# Bypass_FPGA_3V3.net
KiCad netlist of a schematic drawn in Altium Designer
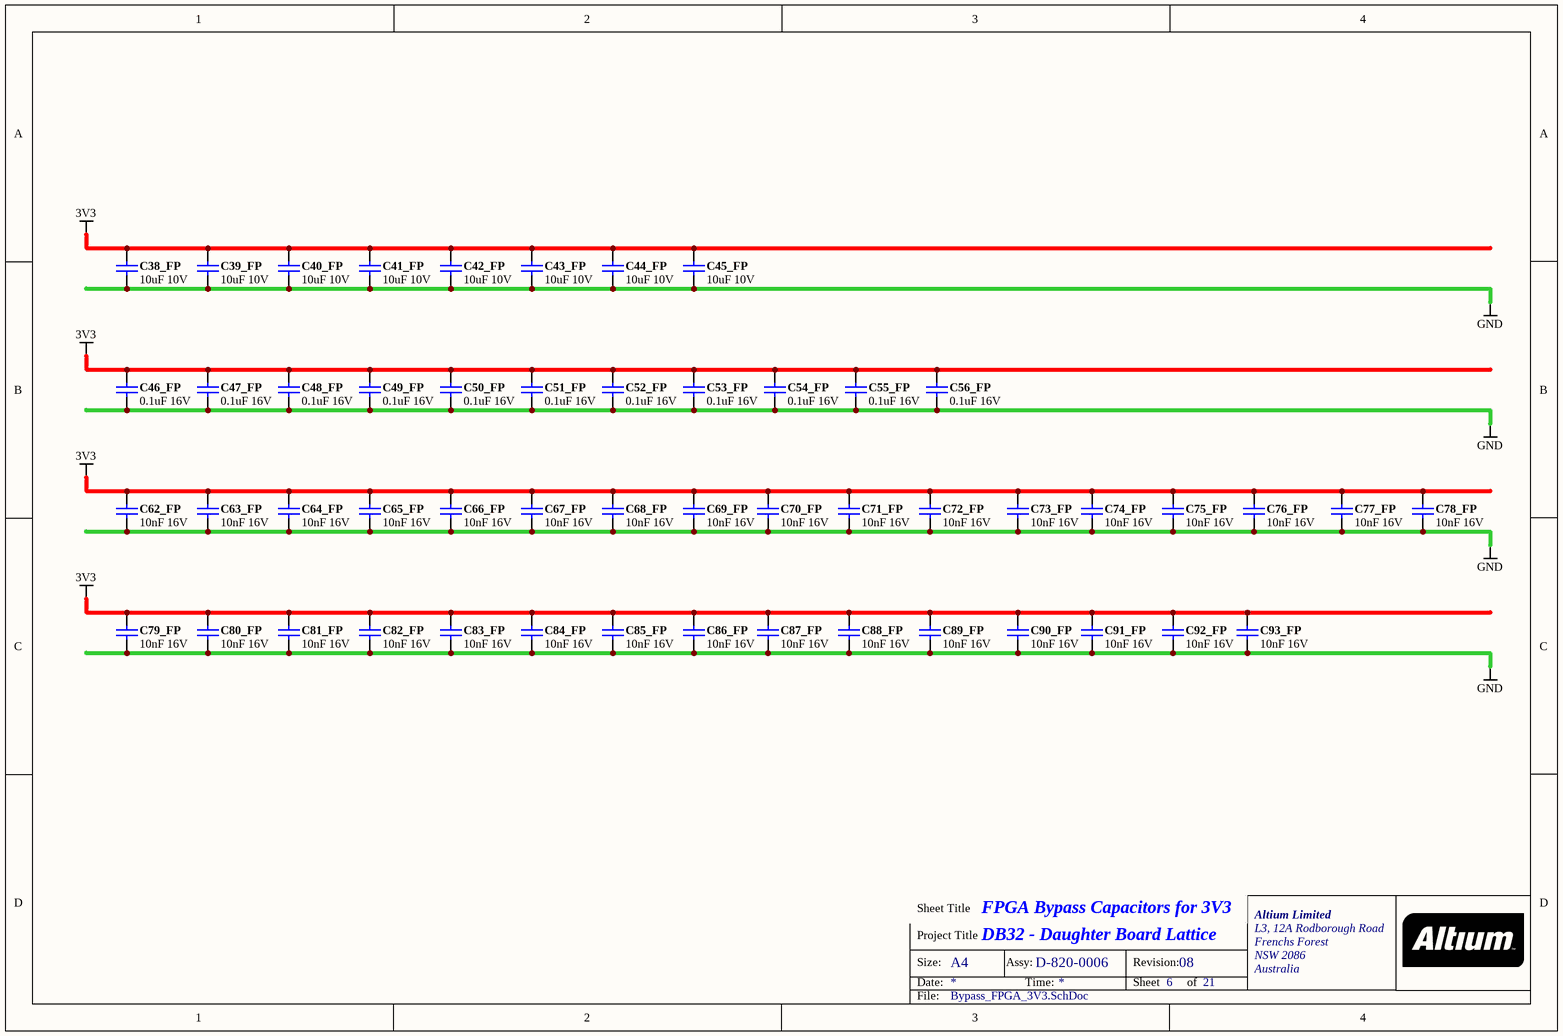
[diagram p0: Bypass_FPGA_3V3.SchDoc]

(export (version "E")
  (design (tool "Eeschema 10.0.6"))
  (components
    (comp (ref "C38_FP")
      (value "10uF 10V")
      (footprint "CAPC2012-STAR")
      (description "Capacitor, Ceramic, 10uF 10% 10V 0805 (2012) X5R")
      (fields (field (name "TOLERANCE") "10 %"))
      (libsource (lib "AltiumDesignLibrary") (part "CAP-NP"))
    )
    (comp (ref "C39_FP")
      (value "10uF 10V")
      (footprint "CAPC2012-STAR")
      (description "Capacitor, Ceramic, 10uF 10% 10V 0805 (2012) X5R")
      (fields (field (name "TOLERANCE") "10 %"))
      (libsource (lib "AltiumDesignLibrary") (part "CAP-NP"))
    )
    (comp (ref "C40_FP")
      (value "10uF 10V")
      (footprint "CAPC2012-STAR")
      (description "Capacitor, Ceramic, 10uF 10% 10V 0805 (2012) X5R")
      (fields (field (name "TOLERANCE") "10 %"))
      (libsource (lib "AltiumDesignLibrary") (part "CAP-NP"))
    )
    (comp (ref "C41_FP")
      (value "10uF 10V")
      (footprint "CAPC2012-STAR")
      (description "Capacitor, Ceramic, 10uF 10% 10V 0805 (2012) X5R")
      (fields (field (name "TOLERANCE") "10 %"))
      (libsource (lib "AltiumDesignLibrary") (part "CAP-NP"))
    )
    (comp (ref "C42_FP")
      (value "10uF 10V")
      (footprint "CAPC2012-STAR")
      (description "Capacitor, Ceramic, 10uF 10% 10V 0805 (2012) X5R")
      (fields (field (name "TOLERANCE") "10 %"))
      (libsource (lib "AltiumDesignLibrary") (part "CAP-NP"))
    )
    (comp (ref "C43_FP")
      (value "10uF 10V")
      (footprint "CAPC2012-STAR")
      (description "Capacitor, Ceramic, 10uF 10% 10V 0805 (2012) X5R")
      (fields (field (name "TOLERANCE") "10 %"))
      (libsource (lib "AltiumDesignLibrary") (part "CAP-NP"))
    )
    (comp (ref "C44_FP")
      (value "10uF 10V")
      (footprint "CAPC2012-STAR")
      (description "Capacitor, Ceramic, 10uF 10% 10V 0805 (2012) X5R")
      (fields (field (name "TOLERANCE") "10 %"))
      (libsource (lib "AltiumDesignLibrary") (part "CAP-NP"))
    )
    (comp (ref "C45_FP")
      (value "10uF 10V")
      (footprint "CAPC2012-STAR")
      (description "Capacitor, Ceramic, 10uF 10% 10V 0805 (2012) X5R")
      (fields (field (name "TOLERANCE") "10 %"))
      (libsource (lib "AltiumDesignLibrary") (part "CAP-NP"))
    )
    (comp (ref "C46_FP")
      (value "0.1uF 16V")
      (footprint "CAPC1005-STAR")
      (description "Capacitor, Ceramic, 0.1uF 10% 16V 0402 (1005) X7R")
      (fields (field (name "TOLERANCE") "10 %"))
      (libsource (lib "AltiumDesignLibrary") (part "CAP-NP"))
    )
    (comp (ref "C47_FP")
      (value "0.1uF 16V")
      (footprint "CAPC1005-STAR")
      (description "Capacitor, Ceramic, 0.1uF 10% 16V 0402 (1005) X7R")
      (fields (field (name "TOLERANCE") "10 %"))
      (libsource (lib "AltiumDesignLibrary") (part "CAP-NP"))
    )
    (comp (ref "C48_FP")
      (value "0.1uF 16V")
      (footprint "CAPC1005-STAR")
      (description "Capacitor, Ceramic, 0.1uF 10% 16V 0402 (1005) X7R")
      (fields (field (name "TOLERANCE") "10 %"))
      (libsource (lib "AltiumDesignLibrary") (part "CAP-NP"))
    )
    (comp (ref "C49_FP")
      (value "0.1uF 16V")
      (footprint "CAPC1005-STAR")
      (description "Capacitor, Ceramic, 0.1uF 10% 16V 0402 (1005) X7R")
      (fields (field (name "TOLERANCE") "10 %"))
      (libsource (lib "AltiumDesignLibrary") (part "CAP-NP"))
    )
    (comp (ref "C50_FP")
      (value "0.1uF 16V")
      (footprint "CAPC1005-STAR")
      (description "Capacitor, Ceramic, 0.1uF 10% 16V 0402 (1005) X7R")
      (fields (field (name "TOLERANCE") "10 %"))
      (libsource (lib "AltiumDesignLibrary") (part "CAP-NP"))
    )
    (comp (ref "C51_FP")
      (value "0.1uF 16V")
      (footprint "CAPC1005-STAR")
      (description "Capacitor, Ceramic, 0.1uF 10% 16V 0402 (1005) X7R")
      (fields (field (name "TOLERANCE") "10 %"))
      (libsource (lib "AltiumDesignLibrary") (part "CAP-NP"))
    )
    (comp (ref "C52_FP")
      (value "0.1uF 16V")
      (footprint "CAPC1005-STAR")
      (description "Capacitor, Ceramic, 0.1uF 10% 16V 0402 (1005) X7R")
      (fields (field (name "TOLERANCE") "10 %"))
      (libsource (lib "AltiumDesignLibrary") (part "CAP-NP"))
    )
    (comp (ref "C53_FP")
      (value "0.1uF 16V")
      (footprint "CAPC1005-STAR")
      (description "Capacitor, Ceramic, 0.1uF 10% 16V 0402 (1005) X7R")
      (fields (field (name "TOLERANCE") "10 %"))
      (libsource (lib "AltiumDesignLibrary") (part "CAP-NP"))
    )
    (comp (ref "C54_FP")
      (value "0.1uF 16V")
      (footprint "CAPC1005-STAR")
      (description "Capacitor, Ceramic, 0.1uF 10% 16V 0402 (1005) X7R")
      (fields (field (name "TOLERANCE") "10 %"))
      (libsource (lib "AltiumDesignLibrary") (part "CAP-NP"))
    )
    (comp (ref "C55_FP")
      (value "0.1uF 16V")
      (footprint "CAPC1005-STAR")
      (description "Capacitor, Ceramic, 0.1uF 10% 16V 0402 (1005) X7R")
      (fields (field (name "TOLERANCE") "10 %"))
      (libsource (lib "AltiumDesignLibrary") (part "CAP-NP"))
    )
    (comp (ref "C56_FP")
      (value "0.1uF 16V")
      (footprint "CAPC1005-STAR")
      (description "Capacitor, Ceramic, 0.1uF 10% 16V 0402 (1005) X7R")
      (fields (field (name "TOLERANCE") "10 %"))
      (libsource (lib "AltiumDesignLibrary") (part "CAP-NP"))
    )
    (comp (ref "C62_FP")
      (value "10nF 16V")
      (footprint "CAPC1005-STAR")
      (description "Capacitor, Ceramic, 10nF 10% 16V 0402 (1005) X7R")
      (fields (field (name "TOLERANCE") "10 %"))
      (libsource (lib "AltiumDesignLibrary") (part "CAP-NP"))
    )
    (comp (ref "C63_FP")
      (value "10nF 16V")
      (footprint "CAPC1005-STAR")
      (description "Capacitor, Ceramic, 10nF 10% 16V 0402 (1005) X7R")
      (fields (field (name "TOLERANCE") "10 %"))
      (libsource (lib "AltiumDesignLibrary") (part "CAP-NP"))
    )
    (comp (ref "C64_FP")
      (value "10nF 16V")
      (footprint "CAPC1005-STAR")
      (description "Capacitor, Ceramic, 10nF 10% 16V 0402 (1005) X7R")
      (fields (field (name "TOLERANCE") "10 %"))
      (libsource (lib "AltiumDesignLibrary") (part "CAP-NP"))
    )
    (comp (ref "C65_FP")
      (value "10nF 16V")
      (footprint "CAPC1005-STAR")
      (description "Capacitor, Ceramic, 10nF 10% 16V 0402 (1005) X7R")
      (fields (field (name "TOLERANCE") "10 %"))
      (libsource (lib "AltiumDesignLibrary") (part "CAP-NP"))
    )
    (comp (ref "C66_FP")
      (value "10nF 16V")
      (footprint "CAPC1005-STAR")
      (description "Capacitor, Ceramic, 10nF 10% 16V 0402 (1005) X7R")
      (fields (field (name "TOLERANCE") "10 %"))
      (libsource (lib "AltiumDesignLibrary") (part "CAP-NP"))
    )
    (comp (ref "C67_FP")
      (value "10nF 16V")
      (footprint "CAPC1005-STAR")
      (description "Capacitor, Ceramic, 10nF 10% 16V 0402 (1005) X7R")
      (fields (field (name "TOLERANCE") "10 %"))
      (libsource (lib "AltiumDesignLibrary") (part "CAP-NP"))
    )
    (comp (ref "C68_FP")
      (value "10nF 16V")
      (footprint "CAPC1005-STAR")
      (description "Capacitor, Ceramic, 10nF 10% 16V 0402 (1005) X7R")
      (fields (field (name "TOLERANCE") "10 %"))
      (libsource (lib "AltiumDesignLibrary") (part "CAP-NP"))
    )
    (comp (ref "C69_FP")
      (value "10nF 16V")
      (footprint "CAPC1005-STAR")
      (description "Capacitor, Ceramic, 10nF 10% 16V 0402 (1005) X7R")
      (fields (field (name "TOLERANCE") "10 %"))
      (libsource (lib "AltiumDesignLibrary") (part "CAP-NP"))
    )
    (comp (ref "C70_FP")
      (value "10nF 16V")
      (footprint "CAPC1005-STAR")
      (description "Capacitor, Ceramic, 10nF 10% 16V 0402 (1005) X7R")
      (fields (field (name "TOLERANCE") "10 %"))
      (libsource (lib "AltiumDesignLibrary") (part "CAP-NP"))
    )
    (comp (ref "C71_FP")
      (value "10nF 16V")
      (footprint "CAPC1005-STAR")
      (description "Capacitor, Ceramic, 10nF 10% 16V 0402 (1005) X7R")
      (fields (field (name "TOLERANCE") "10 %"))
      (libsource (lib "AltiumDesignLibrary") (part "CAP-NP"))
    )
    (comp (ref "C72_FP")
      (value "10nF 16V")
      (footprint "CAPC1005-STAR")
      (description "Capacitor, Ceramic, 10nF 10% 16V 0402 (1005) X7R")
      (fields (field (name "TOLERANCE") "10 %"))
      (libsource (lib "AltiumDesignLibrary") (part "CAP-NP"))
    )
    (comp (ref "C73_FP")
      (value "10nF 16V")
      (footprint "CAPC1005-STAR")
      (description "Capacitor, Ceramic, 10nF 10% 16V 0402 (1005) X7R")
      (fields (field (name "TOLERANCE") "10 %"))
      (libsource (lib "AltiumDesignLibrary") (part "CAP-NP"))
    )
    (comp (ref "C74_FP")
      (value "10nF 16V")
      (footprint "CAPC1005-STAR")
      (description "Capacitor, Ceramic, 10nF 10% 16V 0402 (1005) X7R")
      (fields (field (name "TOLERANCE") "10 %"))
      (libsource (lib "AltiumDesignLibrary") (part "CAP-NP"))
    )
    (comp (ref "C75_FP")
      (value "10nF 16V")
      (footprint "CAPC1005-STAR")
      (description "Capacitor, Ceramic, 10nF 10% 16V 0402 (1005) X7R")
      (fields (field (name "TOLERANCE") "10 %"))
      (libsource (lib "AltiumDesignLibrary") (part "CAP-NP"))
    )
    (comp (ref "C76_FP")
      (value "10nF 16V")
      (footprint "CAPC1005-STAR")
      (description "Capacitor, Ceramic, 10nF 10% 16V 0402 (1005) X7R")
      (fields (field (name "TOLERANCE") "10 %"))
      (libsource (lib "AltiumDesignLibrary") (part "CAP-NP"))
    )
    (comp (ref "C77_FP")
      (value "10nF 16V")
      (footprint "CAPC1005-STAR")
      (description "Capacitor, Ceramic, 10nF 10% 16V 0402 (1005) X7R")
      (fields (field (name "TOLERANCE") "10 %"))
      (libsource (lib "AltiumDesignLibrary") (part "CAP-NP"))
    )
    (comp (ref "C78_FP")
      (value "10nF 16V")
      (footprint "CAPC1005-STAR")
      (description "Capacitor, Ceramic, 10nF 10% 16V 0402 (1005) X7R")
      (fields (field (name "TOLERANCE") "10 %"))
      (libsource (lib "AltiumDesignLibrary") (part "CAP-NP"))
    )
    (comp (ref "C79_FP")
      (value "10nF 16V")
      (footprint "CAPC1005-STAR")
      (description "Capacitor, Ceramic, 10nF 10% 16V 0402 (1005) X7R")
      (fields (field (name "TOLERANCE") "10 %"))
      (libsource (lib "AltiumDesignLibrary") (part "CAP-NP"))
    )
    (comp (ref "C80_FP")
      (value "10nF 16V")
      (footprint "CAPC1005-STAR")
      (description "Capacitor, Ceramic, 10nF 10% 16V 0402 (1005) X7R")
      (fields (field (name "TOLERANCE") "10 %"))
      (libsource (lib "AltiumDesignLibrary") (part "CAP-NP"))
    )
    (comp (ref "C81_FP")
      (value "10nF 16V")
      (footprint "CAPC1005-STAR")
      (description "Capacitor, Ceramic, 10nF 10% 16V 0402 (1005) X7R")
      (fields (field (name "TOLERANCE") "10 %"))
      (libsource (lib "AltiumDesignLibrary") (part "CAP-NP"))
    )
    (comp (ref "C82_FP")
      (value "10nF 16V")
      (footprint "CAPC1005-STAR")
      (description "Capacitor, Ceramic, 10nF 10% 16V 0402 (1005) X7R")
      (fields (field (name "TOLERANCE") "10 %"))
      (libsource (lib "AltiumDesignLibrary") (part "CAP-NP"))
    )
    (comp (ref "C83_FP")
      (value "10nF 16V")
      (footprint "CAPC1005-STAR")
      (description "Capacitor, Ceramic, 10nF 10% 16V 0402 (1005) X7R")
      (fields (field (name "TOLERANCE") "10 %"))
      (libsource (lib "AltiumDesignLibrary") (part "CAP-NP"))
    )
    (comp (ref "C84_FP")
      (value "10nF 16V")
      (footprint "CAPC1005-STAR")
      (description "Capacitor, Ceramic, 10nF 10% 16V 0402 (1005) X7R")
      (fields (field (name "TOLERANCE") "10 %"))
      (libsource (lib "AltiumDesignLibrary") (part "CAP-NP"))
    )
    (comp (ref "C85_FP")
      (value "10nF 16V")
      (footprint "CAPC1005-STAR")
      (description "Capacitor, Ceramic, 10nF 10% 16V 0402 (1005) X7R")
      (fields (field (name "TOLERANCE") "10 %"))
      (libsource (lib "AltiumDesignLibrary") (part "CAP-NP"))
    )
    (comp (ref "C86_FP")
      (value "10nF 16V")
      (footprint "CAPC1005-STAR")
      (description "Capacitor, Ceramic, 10nF 10% 16V 0402 (1005) X7R")
      (fields (field (name "TOLERANCE") "10 %"))
      (libsource (lib "AltiumDesignLibrary") (part "CAP-NP"))
    )
    (comp (ref "C87_FP")
      (value "10nF 16V")
      (footprint "CAPC1005-STAR")
      (description "Capacitor, Ceramic, 10nF 10% 16V 0402 (1005) X7R")
      (fields (field (name "TOLERANCE") "10 %"))
      (libsource (lib "AltiumDesignLibrary") (part "CAP-NP"))
    )
    (comp (ref "C88_FP")
      (value "10nF 16V")
      (footprint "CAPC1005-STAR")
      (description "Capacitor, Ceramic, 10nF 10% 16V 0402 (1005) X7R")
      (fields (field (name "TOLERANCE") "10 %"))
      (libsource (lib "AltiumDesignLibrary") (part "CAP-NP"))
    )
    (comp (ref "C89_FP")
      (value "10nF 16V")
      (footprint "CAPC1005-STAR")
      (description "Capacitor, Ceramic, 10nF 10% 16V 0402 (1005) X7R")
      (fields (field (name "TOLERANCE") "10 %"))
      (libsource (lib "AltiumDesignLibrary") (part "CAP-NP"))
    )
    (comp (ref "C90_FP")
      (value "10nF 16V")
      (footprint "CAPC1005-STAR")
      (description "Capacitor, Ceramic, 10nF 10% 16V 0402 (1005) X7R")
      (fields (field (name "TOLERANCE") "10 %"))
      (libsource (lib "AltiumDesignLibrary") (part "CAP-NP"))
    )
    (comp (ref "C91_FP")
      (value "10nF 16V")
      (footprint "CAPC1005-STAR")
      (description "Capacitor, Ceramic, 10nF 10% 16V 0402 (1005) X7R")
      (fields (field (name "TOLERANCE") "10 %"))
      (libsource (lib "AltiumDesignLibrary") (part "CAP-NP"))
    )
    (comp (ref "C92_FP")
      (value "10nF 16V")
      (footprint "CAPC1005-STAR")
      (description "Capacitor, Ceramic, 10nF 10% 16V 0402 (1005) X7R")
      (fields (field (name "TOLERANCE") "10 %"))
      (libsource (lib "AltiumDesignLibrary") (part "CAP-NP"))
    )
    (comp (ref "C93_FP")
      (value "10nF 16V")
      (footprint "CAPC1005-STAR")
      (description "Capacitor, Ceramic, 10nF 10% 16V 0402 (1005) X7R")
      (fields (field (name "TOLERANCE") "10 %"))
      (libsource (lib "AltiumDesignLibrary") (part "CAP-NP"))
    )
  )
  (nets
    (net (code "1") (name "3V3") (class "Default")
      (node (ref "C38_FP") (pin "1") (pinfunction "1_1") (pintype "passive"))
      (node (ref "C39_FP") (pin "1") (pinfunction "1_1") (pintype "passive"))
      (node (ref "C40_FP") (pin "1") (pinfunction "1_1") (pintype "passive"))
      (node (ref "C41_FP") (pin "1") (pinfunction "1_1") (pintype "passive"))
      (node (ref "C42_FP") (pin "1") (pinfunction "1_1") (pintype "passive"))
      (node (ref "C43_FP") (pin "1") (pinfunction "1_1") (pintype "passive"))
      (node (ref "C44_FP") (pin "1") (pinfunction "1_1") (pintype "passive"))
      (node (ref "C45_FP") (pin "1") (pinfunction "1_1") (pintype "passive"))
      (node (ref "C46_FP") (pin "1") (pinfunction "1_1") (pintype "passive"))
      (node (ref "C47_FP") (pin "1") (pinfunction "1_1") (pintype "passive"))
      (node (ref "C48_FP") (pin "1") (pinfunction "1_1") (pintype "passive"))
      (node (ref "C49_FP") (pin "1") (pinfunction "1_1") (pintype "passive"))
      (node (ref "C50_FP") (pin "1") (pinfunction "1_1") (pintype "passive"))
      (node (ref "C51_FP") (pin "1") (pinfunction "1_1") (pintype "passive"))
      (node (ref "C52_FP") (pin "1") (pinfunction "1_1") (pintype "passive"))
      (node (ref "C53_FP") (pin "1") (pinfunction "1_1") (pintype "passive"))
      (node (ref "C54_FP") (pin "1") (pinfunction "1_1") (pintype "passive"))
      (node (ref "C55_FP") (pin "1") (pinfunction "1_1") (pintype "passive"))
      (node (ref "C56_FP") (pin "1") (pinfunction "1_1") (pintype "passive"))
      (node (ref "C62_FP") (pin "1") (pinfunction "1_1") (pintype "passive"))
      (node (ref "C63_FP") (pin "1") (pinfunction "1_1") (pintype "passive"))
      (node (ref "C64_FP") (pin "1") (pinfunction "1_1") (pintype "passive"))
      (node (ref "C65_FP") (pin "1") (pinfunction "1_1") (pintype "passive"))
      (node (ref "C66_FP") (pin "1") (pinfunction "1_1") (pintype "passive"))
      (node (ref "C67_FP") (pin "1") (pinfunction "1_1") (pintype "passive"))
      (node (ref "C68_FP") (pin "1") (pinfunction "1_1") (pintype "passive"))
      (node (ref "C69_FP") (pin "1") (pinfunction "1_1") (pintype "passive"))
      (node (ref "C70_FP") (pin "1") (pinfunction "1_1") (pintype "passive"))
      (node (ref "C71_FP") (pin "1") (pinfunction "1_1") (pintype "passive"))
      (node (ref "C72_FP") (pin "1") (pinfunction "1_1") (pintype "passive"))
      (node (ref "C73_FP") (pin "1") (pinfunction "1_1") (pintype "passive"))
      (node (ref "C74_FP") (pin "1") (pinfunction "1_1") (pintype "passive"))
      (node (ref "C75_FP") (pin "1") (pinfunction "1_1") (pintype "passive"))
      (node (ref "C76_FP") (pin "1") (pinfunction "1_1") (pintype "passive"))
      (node (ref "C77_FP") (pin "1") (pinfunction "1_1") (pintype "passive"))
      (node (ref "C78_FP") (pin "1") (pinfunction "1_1") (pintype "passive"))
      (node (ref "C79_FP") (pin "1") (pinfunction "1_1") (pintype "passive"))
      (node (ref "C80_FP") (pin "1") (pinfunction "1_1") (pintype "passive"))
      (node (ref "C81_FP") (pin "1") (pinfunction "1_1") (pintype "passive"))
      (node (ref "C82_FP") (pin "1") (pinfunction "1_1") (pintype "passive"))
      (node (ref "C83_FP") (pin "1") (pinfunction "1_1") (pintype "passive"))
      (node (ref "C84_FP") (pin "1") (pinfunction "1_1") (pintype "passive"))
      (node (ref "C85_FP") (pin "1") (pinfunction "1_1") (pintype "passive"))
      (node (ref "C86_FP") (pin "1") (pinfunction "1_1") (pintype "passive"))
      (node (ref "C87_FP") (pin "1") (pinfunction "1_1") (pintype "passive"))
      (node (ref "C88_FP") (pin "1") (pinfunction "1_1") (pintype "passive"))
      (node (ref "C89_FP") (pin "1") (pinfunction "1_1") (pintype "passive"))
      (node (ref "C90_FP") (pin "1") (pinfunction "1_1") (pintype "passive"))
      (node (ref "C91_FP") (pin "1") (pinfunction "1_1") (pintype "passive"))
      (node (ref "C92_FP") (pin "1") (pinfunction "1_1") (pintype "passive"))
      (node (ref "C93_FP") (pin "1") (pinfunction "1_1") (pintype "passive"))
    )
    (net (code "2") (name "GND") (class "Default")
      (node (ref "C38_FP") (pin "2") (pinfunction "2_2") (pintype "passive"))
      (node (ref "C39_FP") (pin "2") (pinfunction "2_2") (pintype "passive"))
      (node (ref "C40_FP") (pin "2") (pinfunction "2_2") (pintype "passive"))
      (node (ref "C41_FP") (pin "2") (pinfunction "2_2") (pintype "passive"))
      (node (ref "C42_FP") (pin "2") (pinfunction "2_2") (pintype "passive"))
      (node (ref "C43_FP") (pin "2") (pinfunction "2_2") (pintype "passive"))
      (node (ref "C44_FP") (pin "2") (pinfunction "2_2") (pintype "passive"))
      (node (ref "C45_FP") (pin "2") (pinfunction "2_2") (pintype "passive"))
      (node (ref "C46_FP") (pin "2") (pinfunction "2_2") (pintype "passive"))
      (node (ref "C47_FP") (pin "2") (pinfunction "2_2") (pintype "passive"))
      (node (ref "C48_FP") (pin "2") (pinfunction "2_2") (pintype "passive"))
      (node (ref "C49_FP") (pin "2") (pinfunction "2_2") (pintype "passive"))
      (node (ref "C50_FP") (pin "2") (pinfunction "2_2") (pintype "passive"))
      (node (ref "C51_FP") (pin "2") (pinfunction "2_2") (pintype "passive"))
      (node (ref "C52_FP") (pin "2") (pinfunction "2_2") (pintype "passive"))
      (node (ref "C53_FP") (pin "2") (pinfunction "2_2") (pintype "passive"))
      (node (ref "C54_FP") (pin "2") (pinfunction "2_2") (pintype "passive"))
      (node (ref "C55_FP") (pin "2") (pinfunction "2_2") (pintype "passive"))
      (node (ref "C56_FP") (pin "2") (pinfunction "2_2") (pintype "passive"))
      (node (ref "C62_FP") (pin "2") (pinfunction "2_2") (pintype "passive"))
      (node (ref "C63_FP") (pin "2") (pinfunction "2_2") (pintype "passive"))
      (node (ref "C64_FP") (pin "2") (pinfunction "2_2") (pintype "passive"))
      (node (ref "C65_FP") (pin "2") (pinfunction "2_2") (pintype "passive"))
      (node (ref "C66_FP") (pin "2") (pinfunction "2_2") (pintype "passive"))
      (node (ref "C67_FP") (pin "2") (pinfunction "2_2") (pintype "passive"))
      (node (ref "C68_FP") (pin "2") (pinfunction "2_2") (pintype "passive"))
      (node (ref "C69_FP") (pin "2") (pinfunction "2_2") (pintype "passive"))
      (node (ref "C70_FP") (pin "2") (pinfunction "2_2") (pintype "passive"))
      (node (ref "C71_FP") (pin "2") (pinfunction "2_2") (pintype "passive"))
      (node (ref "C72_FP") (pin "2") (pinfunction "2_2") (pintype "passive"))
      (node (ref "C73_FP") (pin "2") (pinfunction "2_2") (pintype "passive"))
      (node (ref "C74_FP") (pin "2") (pinfunction "2_2") (pintype "passive"))
      (node (ref "C75_FP") (pin "2") (pinfunction "2_2") (pintype "passive"))
      (node (ref "C76_FP") (pin "2") (pinfunction "2_2") (pintype "passive"))
      (node (ref "C77_FP") (pin "2") (pinfunction "2_2") (pintype "passive"))
      (node (ref "C78_FP") (pin "2") (pinfunction "2_2") (pintype "passive"))
      (node (ref "C79_FP") (pin "2") (pinfunction "2_2") (pintype "passive"))
      (node (ref "C80_FP") (pin "2") (pinfunction "2_2") (pintype "passive"))
      (node (ref "C81_FP") (pin "2") (pinfunction "2_2") (pintype "passive"))
      (node (ref "C82_FP") (pin "2") (pinfunction "2_2") (pintype "passive"))
      (node (ref "C83_FP") (pin "2") (pinfunction "2_2") (pintype "passive"))
      (node (ref "C84_FP") (pin "2") (pinfunction "2_2") (pintype "passive"))
      (node (ref "C85_FP") (pin "2") (pinfunction "2_2") (pintype "passive"))
      (node (ref "C86_FP") (pin "2") (pinfunction "2_2") (pintype "passive"))
      (node (ref "C87_FP") (pin "2") (pinfunction "2_2") (pintype "passive"))
      (node (ref "C88_FP") (pin "2") (pinfunction "2_2") (pintype "passive"))
      (node (ref "C89_FP") (pin "2") (pinfunction "2_2") (pintype "passive"))
      (node (ref "C90_FP") (pin "2") (pinfunction "2_2") (pintype "passive"))
      (node (ref "C91_FP") (pin "2") (pinfunction "2_2") (pintype "passive"))
      (node (ref "C92_FP") (pin "2") (pinfunction "2_2") (pintype "passive"))
      (node (ref "C93_FP") (pin "2") (pinfunction "2_2") (pintype "passive"))
    )
  )
)
